# ARM2toARM3_FPA.net
KiCad netlist of a schematic drawn in Altium Designer
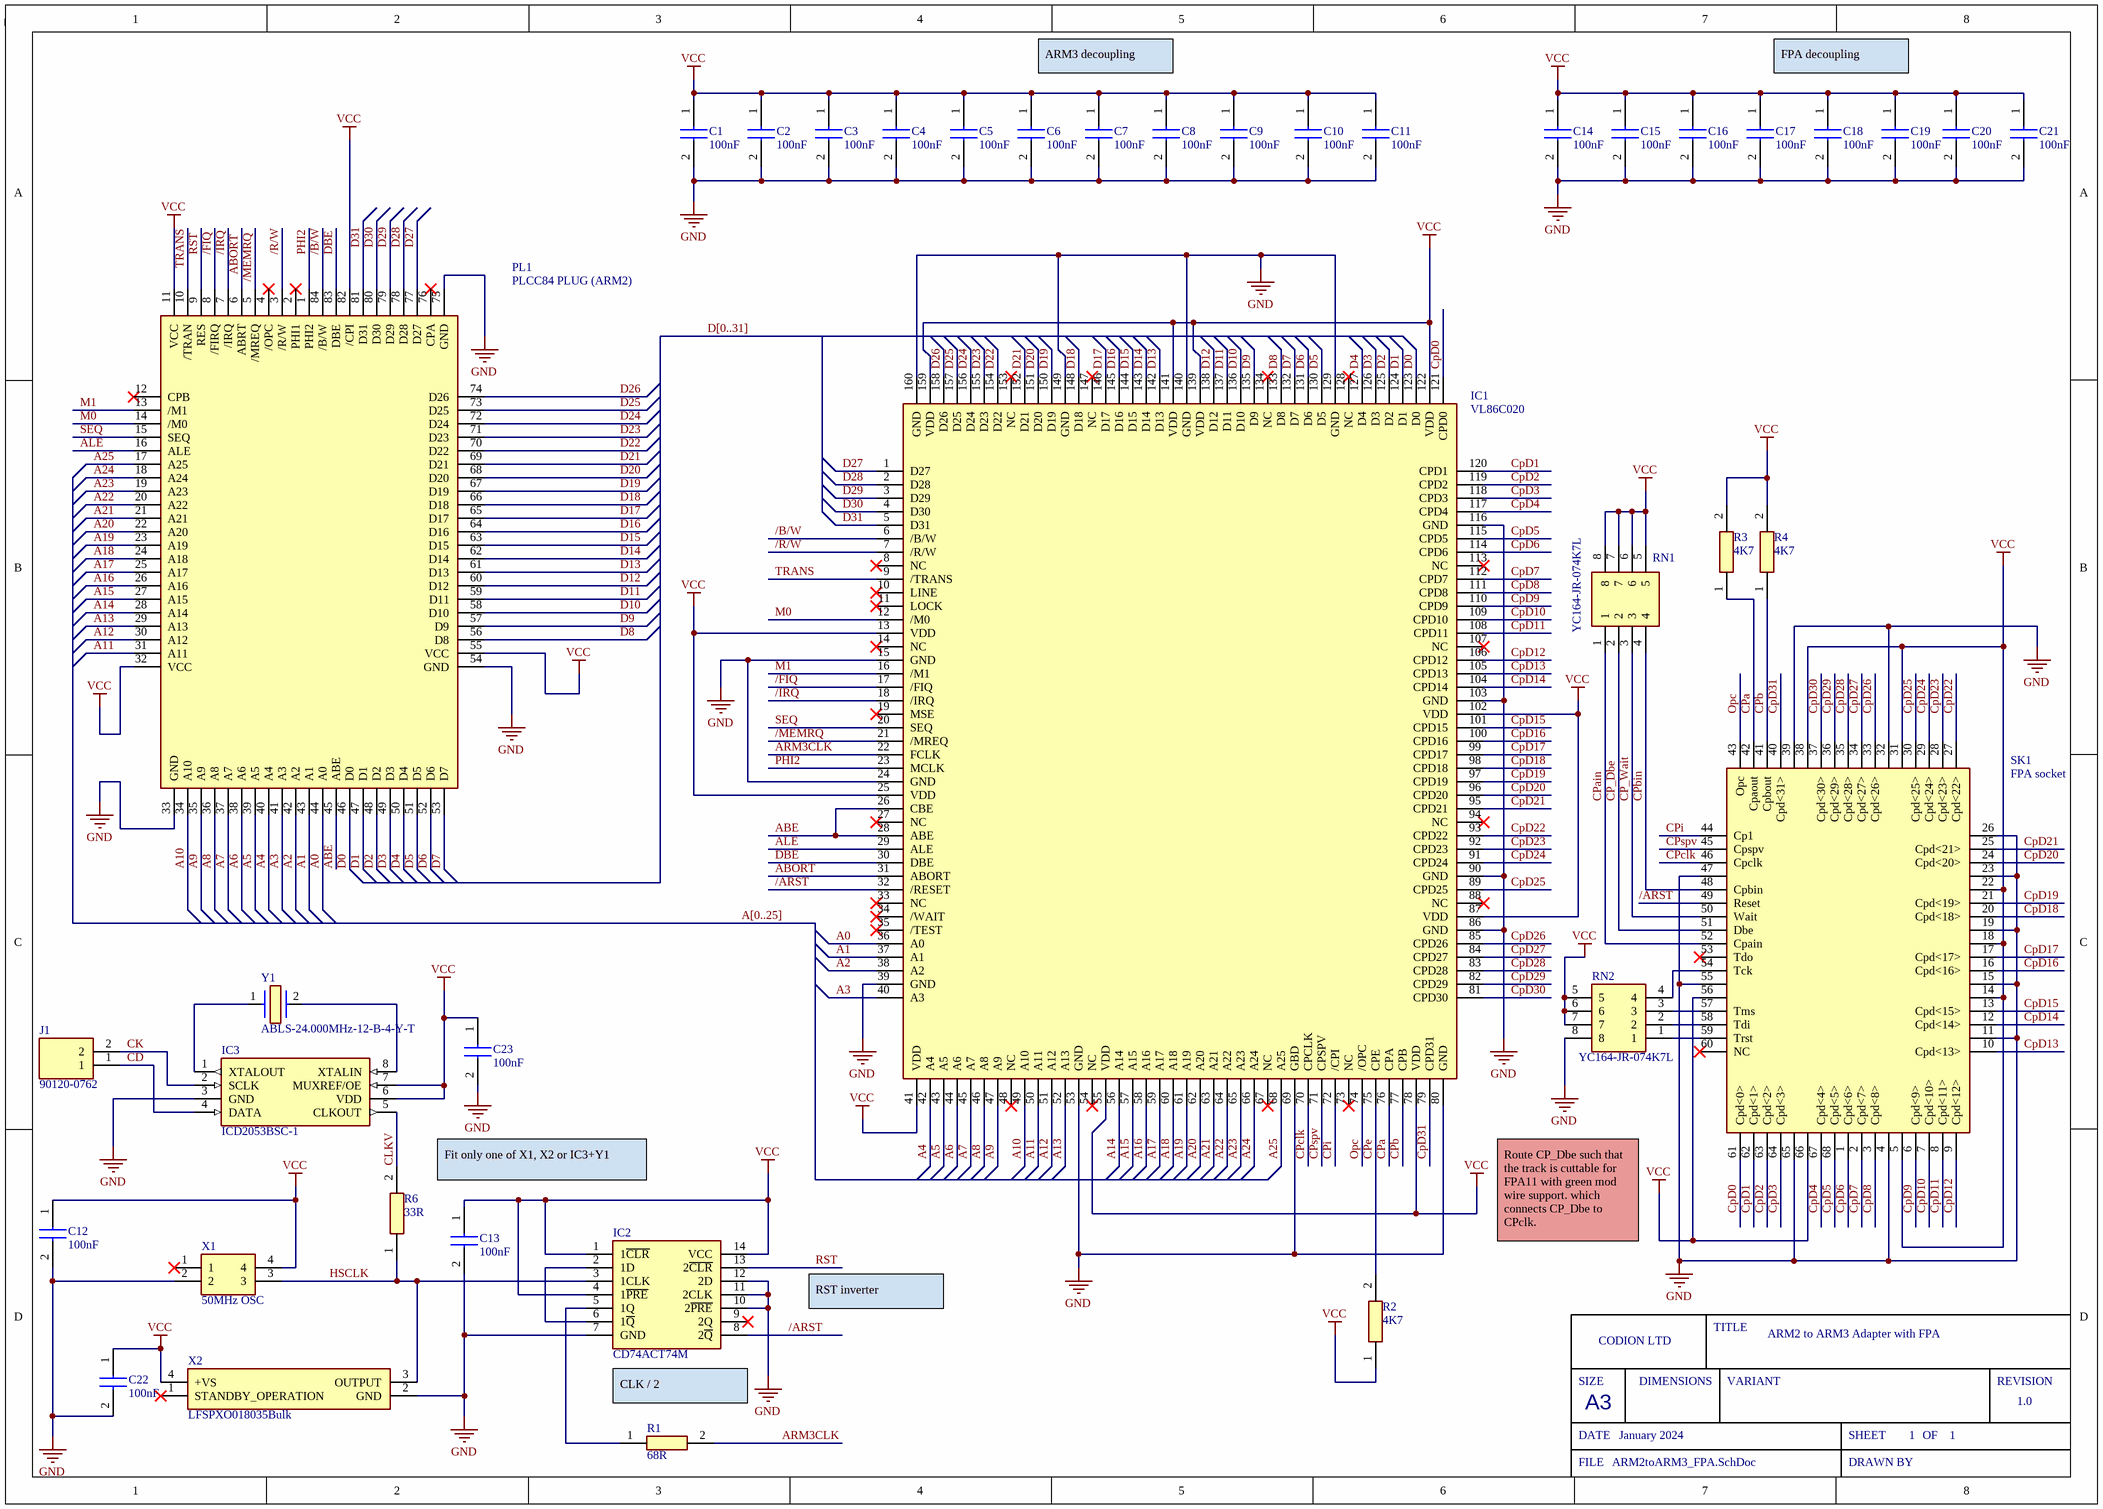
[diagram p0: ARM2toARM3_FPA.SchDoc]

(export (version "E")
  (design (tool "Eeschema 10.0.6"))
  (components
    (comp (ref "C1")
      (value "100nF")
      (footprint "SamacSys:CAPC2012X145N")
      (description "Capacitor")
      (fields
        (field (name "MANUFACTURER_PART_NUMBER") "C2012X7R1H104K125AM")
        (field (name "MOUSER PART NUMBER") "810-C2012X7R1H104KT5")
      )
      (libsource (lib "*") (part "C2012X7R1H104K125AM"))
    )
    (comp (ref "C2")
      (value "100nF")
      (footprint "SamacSys:CAPC2012X145N")
      (description "Capacitor")
      (fields
        (field (name "MANUFACTURER_PART_NUMBER") "C2012X7R1H104K125AM")
        (field (name "MOUSER PART NUMBER") "810-C2012X7R1H104KT5")
      )
      (libsource (lib "*") (part "C2012X7R1H104K125AM"))
    )
    (comp (ref "C3")
      (value "100nF")
      (footprint "SamacSys:CAPC2012X145N")
      (description "Capacitor")
      (fields
        (field (name "MANUFACTURER_PART_NUMBER") "C2012X7R1H104K125AM")
        (field (name "MOUSER PART NUMBER") "810-C2012X7R1H104KT5")
      )
      (libsource (lib "*") (part "C2012X7R1H104K125AM"))
    )
    (comp (ref "C4")
      (value "100nF")
      (footprint "SamacSys:CAPC2012X145N")
      (description "Capacitor")
      (fields
        (field (name "MANUFACTURER_PART_NUMBER") "C2012X7R1H104K125AM")
        (field (name "MOUSER PART NUMBER") "810-C2012X7R1H104KT5")
      )
      (libsource (lib "*") (part "C2012X7R1H104K125AM"))
    )
    (comp (ref "C5")
      (value "100nF")
      (footprint "SamacSys:CAPC2012X145N")
      (description "Capacitor")
      (fields
        (field (name "MANUFACTURER_PART_NUMBER") "C2012X7R1H104K125AM")
        (field (name "MOUSER PART NUMBER") "810-C2012X7R1H104KT5")
      )
      (libsource (lib "*") (part "C2012X7R1H104K125AM"))
    )
    (comp (ref "C6")
      (value "100nF")
      (footprint "SamacSys:CAPC2012X145N")
      (description "Capacitor")
      (fields
        (field (name "MANUFACTURER_PART_NUMBER") "C2012X7R1H104K125AM")
        (field (name "MOUSER PART NUMBER") "810-C2012X7R1H104KT5")
      )
      (libsource (lib "*") (part "C2012X7R1H104K125AM"))
    )
    (comp (ref "C7")
      (value "100nF")
      (footprint "SamacSys:CAPC2012X145N")
      (description "Capacitor")
      (fields
        (field (name "MANUFACTURER_PART_NUMBER") "C2012X7R1H104K125AM")
        (field (name "MOUSER PART NUMBER") "810-C2012X7R1H104KT5")
      )
      (libsource (lib "*") (part "C2012X7R1H104K125AM"))
    )
    (comp (ref "C8")
      (value "100nF")
      (footprint "SamacSys:CAPC2012X145N")
      (description "Capacitor")
      (fields
        (field (name "MANUFACTURER_PART_NUMBER") "C2012X7R1H104K125AM")
        (field (name "MOUSER PART NUMBER") "810-C2012X7R1H104KT5")
      )
      (libsource (lib "*") (part "C2012X7R1H104K125AM"))
    )
    (comp (ref "C9")
      (value "100nF")
      (footprint "SamacSys:CAPC2012X145N")
      (description "Capacitor")
      (fields
        (field (name "MANUFACTURER_PART_NUMBER") "C2012X7R1H104K125AM")
        (field (name "MOUSER PART NUMBER") "810-C2012X7R1H104KT5")
      )
      (libsource (lib "*") (part "C2012X7R1H104K125AM"))
    )
    (comp (ref "C10")
      (value "100nF")
      (footprint "SamacSys:CAPC2012X145N")
      (description "Capacitor")
      (fields
        (field (name "MANUFACTURER_PART_NUMBER") "C2012X7R1H104K125AM")
        (field (name "MOUSER PART NUMBER") "810-C2012X7R1H104KT5")
      )
      (libsource (lib "*") (part "C2012X7R1H104K125AM"))
    )
    (comp (ref "C11")
      (value "100nF")
      (footprint "SamacSys:CAPC2012X145N")
      (description "Capacitor")
      (fields
        (field (name "MANUFACTURER_PART_NUMBER") "C2012X7R1H104K125AM")
        (field (name "MOUSER PART NUMBER") "810-C2012X7R1H104KT5")
      )
      (libsource (lib "*") (part "C2012X7R1H104K125AM"))
    )
    (comp (ref "C12")
      (value "100nF")
      (footprint "SamacSys:CAPC2012X145N")
      (description "Capacitor")
      (fields
        (field (name "MANUFACTURER_PART_NUMBER") "C2012X7R1H104K125AM")
        (field (name "MOUSER PART NUMBER") "810-C2012X7R1H104KT5")
      )
      (libsource (lib "*") (part "C2012X7R1H104K125AM"))
    )
    (comp (ref "C13")
      (value "100nF")
      (footprint "SamacSys:CAPC2012X145N")
      (description "Capacitor")
      (fields
        (field (name "MANUFACTURER_PART_NUMBER") "C2012X7R1H104K125AM")
        (field (name "MOUSER PART NUMBER") "810-C2012X7R1H104KT5")
      )
      (libsource (lib "*") (part "C2012X7R1H104K125AM"))
    )
    (comp (ref "C14")
      (value "100nF")
      (footprint "SamacSys:CAPC2012X145N")
      (description "Capacitor")
      (fields
        (field (name "MANUFACTURER_PART_NUMBER") "C2012X7R1H104K125AM")
        (field (name "MOUSER PART NUMBER") "810-C2012X7R1H104KT5")
      )
      (libsource (lib "*") (part "C2012X7R1H104K125AM"))
    )
    (comp (ref "C15")
      (value "100nF")
      (footprint "SamacSys:CAPC2012X145N")
      (description "Capacitor")
      (fields
        (field (name "MANUFACTURER_PART_NUMBER") "C2012X7R1H104K125AM")
        (field (name "MOUSER PART NUMBER") "810-C2012X7R1H104KT5")
      )
      (libsource (lib "*") (part "C2012X7R1H104K125AM"))
    )
    (comp (ref "C16")
      (value "100nF")
      (footprint "SamacSys:CAPC2012X145N")
      (description "Capacitor")
      (fields
        (field (name "MANUFACTURER_PART_NUMBER") "C2012X7R1H104K125AM")
        (field (name "MOUSER PART NUMBER") "810-C2012X7R1H104KT5")
      )
      (libsource (lib "*") (part "C2012X7R1H104K125AM"))
    )
    (comp (ref "C17")
      (value "100nF")
      (footprint "SamacSys:CAPC2012X145N")
      (description "Capacitor")
      (fields
        (field (name "MANUFACTURER_PART_NUMBER") "C2012X7R1H104K125AM")
        (field (name "MOUSER PART NUMBER") "810-C2012X7R1H104KT5")
      )
      (libsource (lib "*") (part "C2012X7R1H104K125AM"))
    )
    (comp (ref "C18")
      (value "100nF")
      (footprint "SamacSys:CAPC2012X145N")
      (description "Capacitor")
      (fields
        (field (name "MANUFACTURER_PART_NUMBER") "C2012X7R1H104K125AM")
        (field (name "MOUSER PART NUMBER") "810-C2012X7R1H104KT5")
      )
      (libsource (lib "*") (part "C2012X7R1H104K125AM"))
    )
    (comp (ref "C19")
      (value "100nF")
      (footprint "SamacSys:CAPC2012X145N")
      (description "Capacitor")
      (fields
        (field (name "MANUFACTURER_PART_NUMBER") "C2012X7R1H104K125AM")
        (field (name "MOUSER PART NUMBER") "810-C2012X7R1H104KT5")
      )
      (libsource (lib "*") (part "C2012X7R1H104K125AM"))
    )
    (comp (ref "C20")
      (value "100nF")
      (footprint "SamacSys:CAPC2012X145N")
      (description "Capacitor")
      (fields
        (field (name "MANUFACTURER_PART_NUMBER") "C2012X7R1H104K125AM")
        (field (name "MOUSER PART NUMBER") "810-C2012X7R1H104KT5")
      )
      (libsource (lib "*") (part "C2012X7R1H104K125AM"))
    )
    (comp (ref "C21")
      (value "100nF")
      (footprint "SamacSys:CAPC2012X145N")
      (description "Capacitor")
      (fields
        (field (name "MANUFACTURER_PART_NUMBER") "C2012X7R1H104K125AM")
        (field (name "MOUSER PART NUMBER") "810-C2012X7R1H104KT5")
      )
      (libsource (lib "*") (part "C2012X7R1H104K125AM"))
    )
    (comp (ref "C22")
      (value "100nF")
      (footprint "SamacSys:CAPC2012X145N")
      (description "Capacitor")
      (fields
        (field (name "MANUFACTURER_PART_NUMBER") "C2012X7R1H104K125AM")
        (field (name "MOUSER PART NUMBER") "810-C2012X7R1H104KT5")
      )
      (libsource (lib "*") (part "C2012X7R1H104K125AM"))
    )
    (comp (ref "C23")
      (value "100nF")
      (footprint "SamacSys:CAPC2012X145N")
      (description "Capacitor")
      (fields
        (field (name "MANUFACTURER_PART_NUMBER") "C2012X7R1H104K125AM")
        (field (name "MOUSER PART NUMBER") "810-C2012X7R1H104KT5")
      )
      (libsource (lib "*") (part "C2012X7R1H104K125AM"))
    )
    (comp (ref "IC1")
      (value "VL86C020")
      (footprint "SamacSys:QFP65P3120X3120X407-160N")
      (description "ARM3")
      (fields (field (name "MANUFACTURER_PART_NUMBER") "VL86C)20"))
      (libsource (lib "*") (part "SAA7146AH_V4,557"))
    )
    (comp (ref "IC2")
      (value "CD74ACT74M")
      (footprint "SamacSys:SOIC127P600X175-14N")
      (description "Integrated Circuit")
      (fields (field (name "MOUSER PART NUMBER") "595-CD74ACT74M"))
      (libsource (lib "*") (part "CD74ACT74M"))
    )
    (comp (ref "IC3")
      (value "ICD2053BSC-1")
      (footprint "SamacSys:SOIC127P602X173-8N")
      (description "Integrated Circuit")
      (libsource (lib "*") (part "ICD2053BSC-1"))
    )
    (comp (ref "J1")
      (value "90120-0762")
      (footprint "SamacSys:HDRV2W35P0X254_1X2_508X249X560P")
      (description "Connector")
      (fields (field (name "MOUSER PART NUMBER") "538-90120-0762"))
      (libsource (lib "SamacSys") (part "90120-0762"))
    )
    (comp (ref "PL1")
      (value "PLCC84 PLUG (ARM2)")
      (footprint "PLCC84_PLUG")
      (description "PLCC84 Plug")
      (fields (field (name "MANUFACTURER_PART_NUMBER") "W9328"))
      (libsource (lib "ARM2toARM3Adapter") (part "PLCC84_PLUG_ARM2"))
    )
    (comp (ref "R1")
      (value "68R")
      (footprint "SamacSys:RESC2012X50N")
      (description "68R Resistor")
      (fields
        (field (name "MANUFACTURER_PART_NUMBER") "CRCW080568R0FKEA")
        (field (name "MOUSER PART NUMBER") "71-CRCW080568R0FKEA")
      )
      (libsource (lib "*") (part "CRCW080568R0FKEA"))
    )
    (comp (ref "R2")
      (value "4K7")
      (footprint "SamacSys:RESC1005X40N")
      (description "Resistor")
      (fields
        (field (name "MANUFACTURER_PART_NUMBER") "CRCW04024K70FKEDHP")
        (field (name "MOUSER PART NUMBER") "71-CRCW04024K70FKEDH")
      )
      (libsource (lib "*") (part "CRCW04024K70FKEDHP"))
    )
    (comp (ref "R3")
      (value "4K7")
      (footprint "SamacSys:RESC1005X40N")
      (description "Resistor")
      (fields
        (field (name "MANUFACTURER_PART_NUMBER") "CRCW04024K70FKEDHP")
        (field (name "MOUSER PART NUMBER") "71-CRCW04024K70FKEDH")
      )
      (libsource (lib "*") (part "CRCW04024K70FKEDHP"))
    )
    (comp (ref "R4")
      (value "4K7")
      (footprint "SamacSys:RESC1005X40N")
      (description "Resistor")
      (fields
        (field (name "MANUFACTURER_PART_NUMBER") "CRCW04024K70FKEDHP")
        (field (name "MOUSER PART NUMBER") "71-CRCW04024K70FKEDH")
      )
      (libsource (lib "*") (part "CRCW04024K70FKEDHP"))
    )
    (comp (ref "R6")
      (value "33R")
      (footprint "SamacSys:RESC1005X40N")
      (description "Resistor")
      (fields
        (field (name "MANUFACTURER_PART_NUMBER") "CRCW040233R0FKED")
        (field (name "MOUSER PART NUMBER") "71-CRCW0402-33-E3")
      )
      (libsource (lib "SamacSys") (part "CRCW040233R0FKED"))
    )
    (comp (ref "RN1")
      (value "YC164-JR-074K7L")
      (footprint "SamacSys:YC164JR07220RL")
      (description "Resistor Network")
      (fields (field (name "MOUSER PART NUMBER") "603-YC164-JR-074K7L"))
      (libsource (lib "*") (part "YC164-JR-074K7L"))
    )
    (comp (ref "RN2")
      (value "YC164-JR-074K7L")
      (footprint "SamacSys:YC164JR07220RL")
      (description "Resistor Network")
      (fields (field (name "MOUSER PART NUMBER") "603-YC164-JR-074K7L"))
      (libsource (lib "") (part "YC164-JR-074K7L_1"))
    )
    (comp (ref "SK1")
      (value "FPA socket")
      (footprint "Acorn:MEMC_Socket")
      (fields
        (field (name "MANUFACTURER_PART_NUMBER") "8468-21B1-RK-TR")
        (field (name "MOUSER PART NUMBER") "517-8468-21B1-RK-TR")
      )
      (libsource (lib "Acorn") (part "FPA_SKT"))
    )
    (comp (ref "X1")
      (value "50MHz OSC")
      (footprint "SamacSys:DIPS762W56P1524L1778H241Q4N")
      (fields
        (field (name "MANUFACTURER_PART_NUMBER") "1107741")
        (field (name "MOUSER PART NUMBER") "535-1107741")
      )
      (libsource (lib "*") (part "1107741"))
    )
    (comp (ref "X2")
      (value "LFSPXO018035Bulk")
      (footprint "SamacSys:LFSPXO018035Bulk")
      (description "Crystal or Oscillator")
      (fields (field (name "MOUSER PART NUMBER") "449-LFSPXO018035BULK"))
      (libsource (lib "*") (part "LFSPXO018035Bulk"))
    )
    (comp (ref "Y1")
      (value "ABLS-24.000MHz-12-B-4-Y-T")
      (footprint "SamacSys:ABLS")
      (description "Crystal or Oscillator")
      (libsource (lib "*") (part "ABLS-24.000MHz-12-B-4-Y-T"))
    )
  )
  (nets
    (net (code "1") (name "/A0") (class "Default")
      (node (ref "IC1") (pin "36") (pinfunction "A0_36") (pintype "passive"))
      (node (ref "PL1") (pin "44") (pinfunction "A0_44") (pintype "passive"))
    )
    (net (code "2") (name "/A1") (class "Default")
      (node (ref "IC1") (pin "37") (pinfunction "A1_37") (pintype "passive"))
      (node (ref "PL1") (pin "43") (pinfunction "A1_43") (pintype "passive"))
    )
    (net (code "3") (name "/A2") (class "Default")
      (node (ref "IC1") (pin "38") (pinfunction "A2_38") (pintype "passive"))
      (node (ref "PL1") (pin "42") (pinfunction "A2_42") (pintype "passive"))
    )
    (net (code "4") (name "/A3") (class "Default")
      (node (ref "IC1") (pin "40") (pinfunction "A3_40") (pintype "passive"))
      (node (ref "PL1") (pin "41") (pinfunction "A3_41") (pintype "passive"))
    )
    (net (code "5") (name "/A4") (class "Default")
      (node (ref "IC1") (pin "42") (pinfunction "A4_42") (pintype "passive"))
      (node (ref "PL1") (pin "40") (pinfunction "A4_40") (pintype "passive"))
    )
    (net (code "6") (name "/A5") (class "Default")
      (node (ref "IC1") (pin "43") (pinfunction "A5_43") (pintype "passive"))
      (node (ref "PL1") (pin "39") (pinfunction "A5_39") (pintype "passive"))
    )
    (net (code "7") (name "/A6") (class "Default")
      (node (ref "IC1") (pin "44") (pinfunction "A6_44") (pintype "passive"))
      (node (ref "PL1") (pin "38") (pinfunction "A6_38") (pintype "passive"))
    )
    (net (code "8") (name "/A7") (class "Default")
      (node (ref "IC1") (pin "45") (pinfunction "A7_45") (pintype "passive"))
      (node (ref "PL1") (pin "37") (pinfunction "A7_37") (pintype "passive"))
    )
    (net (code "9") (name "/A8") (class "Default")
      (node (ref "IC1") (pin "46") (pinfunction "A8_46") (pintype "passive"))
      (node (ref "PL1") (pin "36") (pinfunction "A8_36") (pintype "passive"))
    )
    (net (code "10") (name "/A9") (class "Default")
      (node (ref "IC1") (pin "47") (pinfunction "A9_47") (pintype "passive"))
      (node (ref "PL1") (pin "35") (pinfunction "A9_35") (pintype "passive"))
    )
    (net (code "11") (name "/A10") (class "Default")
      (node (ref "IC1") (pin "49") (pinfunction "A10_49") (pintype "passive"))
      (node (ref "PL1") (pin "34") (pinfunction "A10_34") (pintype "passive"))
    )
    (net (code "12") (name "/A11") (class "Default")
      (node (ref "IC1") (pin "50") (pinfunction "A11_50") (pintype "passive"))
      (node (ref "PL1") (pin "31") (pinfunction "A11_31") (pintype "passive"))
    )
    (net (code "13") (name "/A12") (class "Default")
      (node (ref "IC1") (pin "51") (pinfunction "A12_51") (pintype "passive"))
      (node (ref "PL1") (pin "30") (pinfunction "A12_30") (pintype "passive"))
    )
    (net (code "14") (name "/A13") (class "Default")
      (node (ref "IC1") (pin "52") (pinfunction "A13_52") (pintype "passive"))
      (node (ref "PL1") (pin "29") (pinfunction "A13_29") (pintype "passive"))
    )
    (net (code "15") (name "/A14") (class "Default")
      (node (ref "IC1") (pin "56") (pinfunction "A14_56") (pintype "passive"))
      (node (ref "PL1") (pin "28") (pinfunction "A14_28") (pintype "passive"))
    )
    (net (code "16") (name "/A15") (class "Default")
      (node (ref "IC1") (pin "57") (pinfunction "A15_57") (pintype "passive"))
      (node (ref "PL1") (pin "27") (pinfunction "A15_27") (pintype "passive"))
    )
    (net (code "17") (name "/A16") (class "Default")
      (node (ref "IC1") (pin "58") (pinfunction "A16_58") (pintype "passive"))
      (node (ref "PL1") (pin "26") (pinfunction "A16_26") (pintype "passive"))
    )
    (net (code "18") (name "/A17") (class "Default")
      (node (ref "IC1") (pin "59") (pinfunction "A17_59") (pintype "passive"))
      (node (ref "PL1") (pin "25") (pinfunction "A17_25") (pintype "passive"))
    )
    (net (code "19") (name "/A18") (class "Default")
      (node (ref "IC1") (pin "60") (pinfunction "A18_60") (pintype "passive"))
      (node (ref "PL1") (pin "24") (pinfunction "A18_24") (pintype "passive"))
    )
    (net (code "20") (name "/A19") (class "Default")
      (node (ref "IC1") (pin "61") (pinfunction "A19_61") (pintype "passive"))
      (node (ref "PL1") (pin "23") (pinfunction "A19_23") (pintype "passive"))
    )
    (net (code "21") (name "/A20") (class "Default")
      (node (ref "IC1") (pin "62") (pinfunction "A20_62") (pintype "passive"))
      (node (ref "PL1") (pin "22") (pinfunction "A20_22") (pintype "passive"))
    )
    (net (code "22") (name "/A21") (class "Default")
      (node (ref "IC1") (pin "63") (pinfunction "A21_63") (pintype "passive"))
      (node (ref "PL1") (pin "21") (pinfunction "A21_21") (pintype "passive"))
    )
    (net (code "23") (name "/A22") (class "Default")
      (node (ref "IC1") (pin "64") (pinfunction "A22_64") (pintype "passive"))
      (node (ref "PL1") (pin "20") (pinfunction "A22_20") (pintype "passive"))
    )
    (net (code "24") (name "/A23") (class "Default")
      (node (ref "IC1") (pin "65") (pinfunction "A23_65") (pintype "passive"))
      (node (ref "PL1") (pin "19") (pinfunction "A23_19") (pintype "passive"))
    )
    (net (code "25") (name "/A24") (class "Default")
      (node (ref "IC1") (pin "66") (pinfunction "A24_66") (pintype "passive"))
      (node (ref "PL1") (pin "18") (pinfunction "A24_18") (pintype "passive"))
    )
    (net (code "26") (name "/A25") (class "Default")
      (node (ref "IC1") (pin "68") (pinfunction "A25_68") (pintype "passive"))
      (node (ref "PL1") (pin "17") (pinfunction "A25_17") (pintype "passive"))
    )
    (net (code "27") (name "/ABE") (class "Default")
      (node (ref "IC1") (pin "26") (pinfunction "CBE_26") (pintype "passive"))
      (node (ref "IC1") (pin "28") (pinfunction "ABE_28") (pintype "passive"))
      (node (ref "PL1") (pin "45") (pinfunction "ABE_45") (pintype "passive"))
    )
    (net (code "28") (name "/ABORT") (class "Default")
      (node (ref "IC1") (pin "31") (pinfunction "ABORT_31") (pintype "passive"))
      (node (ref "PL1") (pin "6") (pinfunction "ABRT_6") (pintype "passive"))
    )
    (net (code "29") (name "/ALE") (class "Default")
      (node (ref "IC1") (pin "29") (pinfunction "ALE_29") (pintype "passive"))
      (node (ref "PL1") (pin "16") (pinfunction "ALE_16") (pintype "passive"))
    )
    (net (code "30") (name "/ARM3CLK") (class "Default")
      (node (ref "IC1") (pin "22") (pinfunction "FCLK_22") (pintype "passive"))
      (node (ref "R1") (pin "2") (pinfunction "2_2") (pintype "passive"))
    )
    (net (code "32") (name "/CD") (class "Default")
      (node (ref "IC3") (pin "4") (pinfunction "DATA_4") (pintype "input"))
      (node (ref "J1") (pin "1") (pinfunction "1_1") (pintype "passive"))
    )
    (net (code "33") (name "/CK") (class "Default")
      (node (ref "IC3") (pin "2") (pinfunction "SCLK_2") (pintype "input"))
      (node (ref "J1") (pin "2") (pinfunction "2_2") (pintype "passive"))
    )
    (net (code "34") (name "/CLKV") (class "Default")
      (node (ref "IC3") (pin "5") (pinfunction "CLKOUT_5") (pintype "output"))
      (node (ref "R6") (pin "2") (pinfunction "2_2") (pintype "passive"))
    )
    (net (code "35") (name "/CP_Dbe") (class "Default")
      (node (ref "RN1") (pin "2") (pinfunction "2_2") (pintype "passive"))
      (node (ref "SK1") (pin "51") (pinfunction "Dbe_51") (pintype "passive"))
    )
    (net (code "36") (name "/CP_Wait") (class "Default")
      (node (ref "RN1") (pin "3") (pinfunction "3_3") (pintype "passive"))
      (node (ref "SK1") (pin "50") (pinfunction "Wait_50") (pintype "passive"))
    )
    (net (code "37") (name "/CPa") (class "Default")
      (node (ref "IC1") (pin "76") (pinfunction "CPA_76") (pintype "passive"))
      (node (ref "R3") (pin "1") (pinfunction "1_1") (pintype "passive"))
      (node (ref "SK1") (pin "42") (pinfunction "Cpaout_42") (pintype "passive"))
    )
    (net (code "38") (name "/CPain") (class "Default")
      (node (ref "RN1") (pin "1") (pinfunction "1_1") (pintype "passive"))
      (node (ref "SK1") (pin "52") (pinfunction "Cpain_52") (pintype "passive"))
    )
    (net (code "39") (name "/CPb") (class "Default")
      (node (ref "IC1") (pin "77") (pinfunction "CPB_77") (pintype "passive"))
      (node (ref "R4") (pin "1") (pinfunction "1_1") (pintype "passive"))
      (node (ref "SK1") (pin "41") (pinfunction "Cpbout_41") (pintype "passive"))
    )
    (net (code "40") (name "/CPbin") (class "Default")
      (node (ref "RN1") (pin "4") (pinfunction "4_4") (pintype "passive"))
      (node (ref "SK1") (pin "48") (pinfunction "Cpbin_48") (pintype "passive"))
    )
    (net (code "41") (name "/CPclk") (class "Default")
      (node (ref "IC1") (pin "70") (pinfunction "CPCLK_70") (pintype "passive"))
      (node (ref "SK1") (pin "46") (pinfunction "Cpclk_46") (pintype "passive"))
    )
    (net (code "42") (name "/CPe") (class "Default")
      (node (ref "IC1") (pin "75") (pinfunction "CPE_75") (pintype "passive"))
      (node (ref "R2") (pin "2") (pinfunction "2_2") (pintype "passive"))
    )
    (net (code "43") (name "/CPi") (class "Default")
      (node (ref "IC1") (pin "72") (pinfunction "/CPI_72") (pintype "passive"))
      (node (ref "SK1") (pin "44") (pinfunction "Cp1_44") (pintype "passive"))
    )
    (net (code "44") (name "/CPspv") (class "Default")
      (node (ref "IC1") (pin "71") (pinfunction "CPSPV_71") (pintype "passive"))
      (node (ref "SK1") (pin "45") (pinfunction "Cpspv_45") (pintype "passive"))
    )
    (net (code "45") (name "/CpD0") (class "Default")
      (node (ref "IC1") (pin "121") (pinfunction "CPD0_121") (pintype "passive"))
      (node (ref "SK1") (pin "61") (pinfunction "Cpd<0>_61") (pintype "passive"))
    )
    (net (code "46") (name "/CpD1") (class "Default")
      (node (ref "IC1") (pin "120") (pinfunction "CPD1_120") (pintype "passive"))
      (node (ref "SK1") (pin "62") (pinfunction "Cpd<1>_62") (pintype "passive"))
    )
    (net (code "47") (name "/CpD2") (class "Default")
      (node (ref "IC1") (pin "119") (pinfunction "CPD2_119") (pintype "passive"))
      (node (ref "SK1") (pin "63") (pinfunction "Cpd<2>_63") (pintype "passive"))
    )
    (net (code "48") (name "/CpD3") (class "Default")
      (node (ref "IC1") (pin "118") (pinfunction "CPD3_118") (pintype "passive"))
      (node (ref "SK1") (pin "64") (pinfunction "Cpd<3>_64") (pintype "passive"))
    )
    (net (code "49") (name "/CpD4") (class "Default")
      (node (ref "IC1") (pin "117") (pinfunction "CPD4_117") (pintype "passive"))
      (node (ref "SK1") (pin "67") (pinfunction "Cpd<4>_67") (pintype "passive"))
    )
    (net (code "50") (name "/CpD5") (class "Default")
      (node (ref "IC1") (pin "115") (pinfunction "CPD5_115") (pintype "passive"))
      (node (ref "SK1") (pin "68") (pinfunction "Cpd<5>_68") (pintype "passive"))
    )
    (net (code "51") (name "/CpD6") (class "Default")
      (node (ref "IC1") (pin "114") (pinfunction "CPD6_114") (pintype "passive"))
      (node (ref "SK1") (pin "1") (pinfunction "Cpd<6>_1") (pintype "passive"))
    )
    (net (code "52") (name "/CpD7") (class "Default")
      (node (ref "IC1") (pin "112") (pinfunction "CPD7_112") (pintype "passive"))
      (node (ref "SK1") (pin "2") (pinfunction "Cpd<7>_2") (pintype "passive"))
    )
    (net (code "53") (name "/CpD8") (class "Default")
      (node (ref "IC1") (pin "111") (pinfunction "CPD8_111") (pintype "passive"))
      (node (ref "SK1") (pin "3") (pinfunction "Cpd<8>_3") (pintype "passive"))
    )
    (net (code "54") (name "/CpD9") (class "Default")
      (node (ref "IC1") (pin "110") (pinfunction "CPD9_110") (pintype "passive"))
      (node (ref "SK1") (pin "6") (pinfunction "Cpd<9>_6") (pintype "passive"))
    )
    (net (code "55") (name "/CpD10") (class "Default")
      (node (ref "IC1") (pin "109") (pinfunction "CPD10_109") (pintype "passive"))
      (node (ref "SK1") (pin "7") (pinfunction "Cpd<10>_7") (pintype "passive"))
    )
    (net (code "56") (name "/CpD11") (class "Default")
      (node (ref "IC1") (pin "108") (pinfunction "CPD11_108") (pintype "passive"))
      (node (ref "SK1") (pin "8") (pinfunction "Cpd<11>_8") (pintype "passive"))
    )
    (net (code "57") (name "/CpD12") (class "Default")
      (node (ref "IC1") (pin "106") (pinfunction "CPD12_106") (pintype "passive"))
      (node (ref "SK1") (pin "9") (pinfunction "Cpd<12>_9") (pintype "passive"))
    )
    (net (code "58") (name "/CpD13") (class "Default")
      (node (ref "IC1") (pin "105") (pinfunction "CPD13_105") (pintype "passive"))
      (node (ref "SK1") (pin "10") (pinfunction "Cpd<13>_10") (pintype "passive"))
    )
    (net (code "59") (name "/CpD14") (class "Default")
      (node (ref "IC1") (pin "104") (pinfunction "CPD14_104") (pintype "passive"))
      (node (ref "SK1") (pin "12") (pinfunction "Cpd<14>_12") (pintype "passive"))
    )
    (net (code "60") (name "/CpD15") (class "Default")
      (node (ref "IC1") (pin "101") (pinfunction "CPD15_101") (pintype "passive"))
      (node (ref "SK1") (pin "13") (pinfunction "Cpd<15>_13") (pintype "passive"))
    )
    (net (code "61") (name "/CpD16") (class "Default")
      (node (ref "IC1") (pin "100") (pinfunction "CPD16_100") (pintype "passive"))
      (node (ref "SK1") (pin "16") (pinfunction "Cpd<16>_16") (pintype "passive"))
    )
    (net (code "62") (name "/CpD17") (class "Default")
      (node (ref "IC1") (pin "99") (pinfunction "CPD17_99") (pintype "passive"))
      (node (ref "SK1") (pin "17") (pinfunction "Cpd<17>_17") (pintype "passive"))
    )
    (net (code "63") (name "/CpD18") (class "Default")
      (node (ref "IC1") (pin "98") (pinfunction "CPD18_98") (pintype "passive"))
      (node (ref "SK1") (pin "20") (pinfunction "Cpd<18>_20") (pintype "passive"))
    )
    (net (code "64") (name "/CpD19") (class "Default")
      (node (ref "IC1") (pin "97") (pinfunction "CPD19_97") (pintype "passive"))
      (node (ref "SK1") (pin "21") (pinfunction "Cpd<19>_21") (pintype "passive"))
    )
    (net (code "65") (name "/CpD20") (class "Default")
      (node (ref "IC1") (pin "96") (pinfunction "CPD20_96") (pintype "passive"))
      (node (ref "SK1") (pin "24") (pinfunction "Cpd<20>_24") (pintype "passive"))
    )
    (net (code "66") (name "/CpD21") (class "Default")
      (node (ref "IC1") (pin "95") (pinfunction "CPD21_95") (pintype "passive"))
      (node (ref "SK1") (pin "25") (pinfunction "Cpd<21>_25") (pintype "passive"))
    )
    (net (code "67") (name "/CpD22") (class "Default")
      (node (ref "IC1") (pin "93") (pinfunction "CPD22_93") (pintype "passive"))
      (node (ref "SK1") (pin "27") (pinfunction "Cpd<22>_27") (pintype "passive"))
    )
    (net (code "68") (name "/CpD23") (class "Default")
      (node (ref "IC1") (pin "92") (pinfunction "CPD23_92") (pintype "passive"))
      (node (ref "SK1") (pin "28") (pinfunction "Cpd<23>_28") (pintype "passive"))
    )
    (net (code "69") (name "/CpD24") (class "Default")
      (node (ref "IC1") (pin "91") (pinfunction "CPD24_91") (pintype "passive"))
      (node (ref "SK1") (pin "29") (pinfunction "Cpd<24>_29") (pintype "passive"))
    )
    (net (code "70") (name "/CpD25") (class "Default")
      (node (ref "IC1") (pin "89") (pinfunction "CPD25_89") (pintype "passive"))
      (node (ref "SK1") (pin "30") (pinfunction "Cpd<25>_30") (pintype "passive"))
    )
    (net (code "71") (name "/CpD26") (class "Default")
      (node (ref "IC1") (pin "85") (pinfunction "CPD26_85") (pintype "passive"))
      (node (ref "SK1") (pin "33") (pinfunction "Cpd<26>_33") (pintype "passive"))
    )
    (net (code "72") (name "/CpD27") (class "Default")
      (node (ref "IC1") (pin "84") (pinfunction "CPD27_84") (pintype "passive"))
      (node (ref "SK1") (pin "34") (pinfunction "Cpd<27>_34") (pintype "passive"))
    )
    (net (code "73") (name "/CpD28") (class "Default")
      (node (ref "IC1") (pin "83") (pinfunction "CPD28_83") (pintype "passive"))
      (node (ref "SK1") (pin "35") (pinfunction "Cpd<28>_35") (pintype "passive"))
    )
    (net (code "74") (name "/CpD29") (class "Default")
      (node (ref "IC1") (pin "82") (pinfunction "CPD29_82") (pintype "passive"))
      (node (ref "SK1") (pin "36") (pinfunction "Cpd<29>_36") (pintype "passive"))
    )
    (net (code "75") (name "/CpD30") (class "Default")
      (node (ref "IC1") (pin "81") (pinfunction "CPD30_81") (pintype "passive"))
      (node (ref "SK1") (pin "37") (pinfunction "Cpd<30>_37") (pintype "passive"))
    )
    (net (code "76") (name "/CpD31") (class "Default")
      (node (ref "IC1") (pin "79") (pinfunction "CPD31_79") (pintype "passive"))
      (node (ref "SK1") (pin "40") (pinfunction "Cpd<31>_40") (pintype "passive"))
    )
    (net (code "77") (name "/D0") (class "Default")
      (node (ref "IC1") (pin "123") (pinfunction "D0_123") (pintype "passive"))
      (node (ref "PL1") (pin "46") (pinfunction "D0_46") (pintype "passive"))
    )
    (net (code "78") (name "/D1") (class "Default")
      (node (ref "IC1") (pin "124") (pinfunction "D1_124") (pintype "passive"))
      (node (ref "PL1") (pin "47") (pinfunction "D1_47") (pintype "passive"))
    )
    (net (code "79") (name "/D2") (class "Default")
      (node (ref "IC1") (pin "125") (pinfunction "D2_125") (pintype "passive"))
      (node (ref "PL1") (pin "48") (pinfunction "D2_48") (pintype "passive"))
    )
    (net (code "80") (name "/D3") (class "Default")
      (node (ref "IC1") (pin "126") (pinfunction "D3_126") (pintype "passive"))
      (node (ref "PL1") (pin "49") (pinfunction "D3_49") (pintype "passive"))
    )
    (net (code "81") (name "/D4") (class "Default")
      (node (ref "IC1") (pin "127") (pinfunction "D4_127") (pintype "passive"))
      (node (ref "PL1") (pin "50") (pinfunction "D4_50") (pintype "passive"))
    )
    (net (code "82") (name "/D5") (class "Default")
      (node (ref "IC1") (pin "130") (pinfunction "D5_130") (pintype "passive"))
      (node (ref "PL1") (pin "51") (pinfunction "D5_51") (pintype "passive"))
    )
    (net (code "83") (name "/D6") (class "Default")
      (node (ref "IC1") (pin "131") (pinfunction "D6_131") (pintype "passive"))
      (node (ref "PL1") (pin "52") (pinfunction "D6_52") (pintype "passive"))
    )
    (net (code "84") (name "/D7") (class "Default")
      (node (ref "IC1") (pin "132") (pinfunction "D7_132") (pintype "passive"))
      (node (ref "PL1") (pin "53") (pinfunction "D7_53") (pintype "passive"))
    )
    (net (code "85") (name "/D8") (class "Default")
      (node (ref "IC1") (pin "133") (pinfunction "D8_133") (pintype "passive"))
      (node (ref "PL1") (pin "56") (pinfunction "D8_56") (pintype "passive"))
    )
    (net (code "86") (name "/D9") (class "Default")
      (node (ref "IC1") (pin "135") (pinfunction "D9_135") (pintype "passive"))
      (node (ref "PL1") (pin "57") (pinfunction "D9_57") (pintype "passive"))
    )
    (net (code "87") (name "/D10") (class "Default")
      (node (ref "IC1") (pin "136") (pinfunction "D10_136") (pintype "passive"))
      (node (ref "PL1") (pin "58") (pinfunction "D10_58") (pintype "passive"))
    )
    (net (code "88") (name "/D11") (class "Default")
      (node (ref "IC1") (pin "137") (pinfunction "D11_137") (pintype "passive"))
      (node (ref "PL1") (pin "59") (pinfunction "D11_59") (pintype "passive"))
    )
    (net (code "89") (name "/D12") (class "Default")
      (node (ref "IC1") (pin "138") (pinfunction "D12_138") (pintype "passive"))
      (node (ref "PL1") (pin "60") (pinfunction "D12_60") (pintype "passive"))
    )
    (net (code "90") (name "/D13") (class "Default")
      (node (ref "IC1") (pin "142") (pinfunction "D13_142") (pintype "passive"))
      (node (ref "PL1") (pin "61") (pinfunction "D13_61") (pintype "passive"))
    )
    (net (code "91") (name "/D14") (class "Default")
      (node (ref "IC1") (pin "143") (pinfunction "D14_143") (pintype "passive"))
      (node (ref "PL1") (pin "62") (pinfunction "D14_62") (pintype "passive"))
    )
    (net (code "92") (name "/D15") (class "Default")
      (node (ref "IC1") (pin "144") (pinfunction "D15_144") (pintype "passive"))
      (node (ref "PL1") (pin "63") (pinfunction "D15_63") (pintype "passive"))
    )
    (net (code "93") (name "/D16") (class "Default")
      (node (ref "IC1") (pin "145") (pinfunction "D16_145") (pintype "passive"))
      (node (ref "PL1") (pin "64") (pinfunction "D16_64") (pintype "passive"))
    )
    (net (code "94") (name "/D17") (class "Default")
      (node (ref "IC1") (pin "146") (pinfunction "D17_146") (pintype "passive"))
      (node (ref "PL1") (pin "65") (pinfunction "D17_65") (pintype "passive"))
    )
    (net (code "95") (name "/D18") (class "Default")
      (node (ref "IC1") (pin "148") (pinfunction "D18_148") (pintype "passive"))
      (node (ref "PL1") (pin "66") (pinfunction "D18_66") (pintype "passive"))
    )
    (net (code "96") (name "/D19") (class "Default")
      (node (ref "IC1") (pin "150") (pinfunction "D19_150") (pintype "passive"))
      (node (ref "PL1") (pin "67") (pinfunction "D19_67") (pintype "passive"))
    )
    (net (code "97") (name "/D20") (class "Default")
      (node (ref "IC1") (pin "151") (pinfunction "D20_151") (pintype "passive"))
      (node (ref "PL1") (pin "68") (pinfunction "D20_68") (pintype "passive"))
    )
    (net (code "98") (name "/D21") (class "Default")
      (node (ref "IC1") (pin "152") (pinfunction "D21_152") (pintype "passive"))
      (node (ref "PL1") (pin "69") (pinfunction "D21_69") (pintype "passive"))
    )
    (net (code "99") (name "/D22") (class "Default")
      (node (ref "IC1") (pin "154") (pinfunction "D22_154") (pintype "passive"))
      (node (ref "PL1") (pin "70") (pinfunction "D22_70") (pintype "passive"))
    )
    (net (code "100") (name "/D23") (class "Default")
      (node (ref "IC1") (pin "155") (pinfunction "D23_155") (pintype "passive"))
      (node (ref "PL1") (pin "71") (pinfunction "D23_71") (pintype "passive"))
    )
    (net (code "101") (name "/D24") (class "Default")
      (node (ref "IC1") (pin "156") (pinfunction "D24_156") (pintype "passive"))
      (node (ref "PL1") (pin "72") (pinfunction "D24_72") (pintype "passive"))
    )
    (net (code "102") (name "/D25") (class "Default")
      (node (ref "IC1") (pin "157") (pinfunction "D25_157") (pintype "passive"))
      (node (ref "PL1") (pin "73") (pinfunction "D25_73") (pintype "passive"))
    )
    (net (code "103") (name "/D26") (class "Default")
      (node (ref "IC1") (pin "158") (pinfunction "D26_158") (pintype "passive"))
      (node (ref "PL1") (pin "74") (pinfunction "D26_74") (pintype "passive"))
    )
    (net (code "104") (name "/D27") (class "Default")
      (node (ref "IC1") (pin "1") (pinfunction "D27_1") (pintype "passive"))
      (node (ref "PL1") (pin "77") (pinfunction "D27_77") (pintype "passive"))
    )
    (net (code "105") (name "/D28") (class "Default")
      (node (ref "IC1") (pin "2") (pinfunction "D28_2") (pintype "passive"))
      (node (ref "PL1") (pin "78") (pinfunction "D28_78") (pintype "passive"))
    )
    (net (code "106") (name "/D29") (class "Default")
      (node (ref "IC1") (pin "3") (pinfunction "D29_3") (pintype "passive"))
      (node (ref "PL1") (pin "79") (pinfunction "D29_79") (pintype "passive"))
    )
    (net (code "107") (name "/D30") (class "Default")
      (node (ref "IC1") (pin "4") (pinfunction "D30_4") (pintype "passive"))
      (node (ref "PL1") (pin "80") (pinfunction "D30_80") (pintype "passive"))
    )
    (net (code "108") (name "/D31") (class "Default")
      (node (ref "IC1") (pin "5") (pinfunction "D31_5") (pintype "passive"))
      (node (ref "PL1") (pin "81") (pinfunction "D31_81") (pintype "passive"))
    )
    (net (code "109") (name "/DBE") (class "Default")
      (node (ref "IC1") (pin "30") (pinfunction "DBE_30") (pintype "passive"))
      (node (ref "PL1") (pin "83") (pinfunction "DBE_83") (pintype "passive"))
    )
    (net (code "111") (name "/HSCLK") (class "Default")
      (node (ref "IC2") (pin "3") (pinfunction "1CLK_3") (pintype "passive"))
      (node (ref "R6") (pin "1") (pinfunction "1_1") (pintype "passive"))
      (node (ref "X1") (pin "3") (pinfunction "3_3") (pintype "passive"))
      (node (ref "X2") (pin "3") (pinfunction "OUTPUT_3") (pintype "passive"))
    )
    (net (code "112") (name "/M0") (class "Default")
      (node (ref "IC1") (pin "12") (pinfunction "/M0_12") (pintype "passive"))
      (node (ref "PL1") (pin "14") (pinfunction "/M0_14") (pintype "passive"))
    )
    (net (code "113") (name "/M1") (class "Default")
      (node (ref "IC1") (pin "16") (pinfunction "/M1_16") (pintype "passive"))
      (node (ref "PL1") (pin "13") (pinfunction "/M1_13") (pintype "passive"))
    )
    (net (code "114") (name "/Opc") (class "Default")
      (node (ref "IC1") (pin "74") (pinfunction "/OPC_74") (pintype "passive"))
      (node (ref "SK1") (pin "43") (pinfunction "Opc_43") (pintype "passive"))
    )
    (net (code "115") (name "/PHI2") (class "Default")
      (node (ref "IC1") (pin "23") (pinfunction "MCLK_23") (pintype "passive"))
      (node (ref "PL1") (pin "1") (pinfunction "PHI2_1") (pintype "passive"))
    )
    (net (code "116") (name "/RST") (class "Default")
      (node (ref "IC2") (pin "13") (pinfunction "2~{CLR}_13") (pintype "passive"))
      (node (ref "PL1") (pin "9") (pinfunction "RES_9") (pintype "passive"))
    )
    (net (code "117") (name "/SEQ") (class "Default")
      (node (ref "IC1") (pin "20") (pinfunction "SEQ_20") (pintype "passive"))
      (node (ref "PL1") (pin "15") (pinfunction "SEQ_15") (pintype "passive"))
    )
    (net (code "118") (name "/TRANS") (class "Default")
      (node (ref "IC1") (pin "9") (pinfunction "/TRANS_9") (pintype "passive"))
      (node (ref "PL1") (pin "10") (pinfunction "/TRAN_10") (pintype "passive"))
    )
    (net (code "119") (name "/{slash}ARST") (class "Default")
      (node (ref "IC1") (pin "32") (pinfunction "/RESET_32") (pintype "passive"))
      (node (ref "IC2") (pin "8") (pinfunction "2~{Q}_8") (pintype "passive"))
      (node (ref "SK1") (pin "49") (pinfunction "Reset_49") (pintype "passive"))
    )
    (net (code "120") (name "/{slash}B{slash}W") (class "Default")
      (node (ref "IC1") (pin "6") (pinfunction "/B/W_6") (pintype "passive"))
      (node (ref "PL1") (pin "84") (pinfunction "/B/W_84") (pintype "passive"))
    )
    (net (code "121") (name "/{slash}FIQ") (class "Default")
      (node (ref "IC1") (pin "17") (pinfunction "/FIQ_17") (pintype "passive"))
      (node (ref "PL1") (pin "8") (pinfunction "/FIRQ_8") (pintype "passive"))
    )
    (net (code "122") (name "/{slash}IRQ") (class "Default")
      (node (ref "IC1") (pin "18") (pinfunction "/IRQ_18") (pintype "passive"))
      (node (ref "PL1") (pin "7") (pinfunction "/IRQ_7") (pintype "passive"))
    )
    (net (code "123") (name "/{slash}MEMRQ") (class "Default")
      (node (ref "IC1") (pin "21") (pinfunction "/MREQ_21") (pintype "passive"))
      (node (ref "PL1") (pin "5") (pinfunction "/MREQ_5") (pintype "passive"))
    )
    (net (code "124") (name "/{slash}R{slash}W") (class "Default")
      (node (ref "IC1") (pin "7") (pinfunction "/R/W_7") (pintype "passive"))
      (node (ref "PL1") (pin "3") (pinfunction "/R/W_3") (pintype "passive"))
    )
    (net (code "125") (name "GND") (class "Default")
      (node (ref "C1") (pin "2") (pinfunction "2_2") (pintype "passive"))
      (node (ref "C10") (pin "2") (pinfunction "2_2") (pintype "passive"))
      (node (ref "C11") (pin "2") (pinfunction "2_2") (pintype "passive"))
      (node (ref "C12") (pin "2") (pinfunction "2_2") (pintype "passive"))
      (node (ref "C13") (pin "2") (pinfunction "2_2") (pintype "passive"))
      (node (ref "C14") (pin "2") (pinfunction "2_2") (pintype "passive"))
      (node (ref "C15") (pin "2") (pinfunction "2_2") (pintype "passive"))
      (node (ref "C16") (pin "2") (pinfunction "2_2") (pintype "passive"))
      (node (ref "C17") (pin "2") (pinfunction "2_2") (pintype "passive"))
      (node (ref "C18") (pin "2") (pinfunction "2_2") (pintype "passive"))
      (node (ref "C19") (pin "2") (pinfunction "2_2") (pintype "passive"))
      (node (ref "C2") (pin "2") (pinfunction "2_2") (pintype "passive"))
      (node (ref "C20") (pin "2") (pinfunction "2_2") (pintype "passive"))
      (node (ref "C21") (pin "2") (pinfunction "2_2") (pintype "passive"))
      (node (ref "C22") (pin "2") (pinfunction "2_2") (pintype "passive"))
      (node (ref "C23") (pin "2") (pinfunction "2_2") (pintype "passive"))
      (node (ref "C3") (pin "2") (pinfunction "2_2") (pintype "passive"))
      (node (ref "C4") (pin "2") (pinfunction "2_2") (pintype "passive"))
      (node (ref "C5") (pin "2") (pinfunction "2_2") (pintype "passive"))
      (node (ref "C6") (pin "2") (pinfunction "2_2") (pintype "passive"))
      (node (ref "C7") (pin "2") (pinfunction "2_2") (pintype "passive"))
      (node (ref "C8") (pin "2") (pinfunction "2_2") (pintype "passive"))
      (node (ref "C9") (pin "2") (pinfunction "2_2") (pintype "passive"))
      (node (ref "IC1") (pin "103") (pinfunction "GND_103") (pintype "passive"))
      (node (ref "IC1") (pin "116") (pinfunction "GND_116") (pintype "passive"))
      (node (ref "IC1") (pin "129") (pinfunction "GND_129") (pintype "passive"))
      (node (ref "IC1") (pin "140") (pinfunction "GND_140") (pintype "passive"))
      (node (ref "IC1") (pin "149") (pinfunction "GND_149") (pintype "passive"))
      (node (ref "IC1") (pin "15") (pinfunction "GND_15") (pintype "passive"))
      (node (ref "IC1") (pin "160") (pinfunction "GND_160") (pintype "passive"))
      (node (ref "IC1") (pin "24") (pinfunction "GND_24") (pintype "passive"))
      (node (ref "IC1") (pin "39") (pinfunction "GND_39") (pintype "passive"))
      (node (ref "IC1") (pin "53") (pinfunction "GND_53") (pintype "passive"))
      (node (ref "IC1") (pin "69") (pinfunction "GBD_69") (pintype "passive"))
      (node (ref "IC1") (pin "80") (pinfunction "GND_80") (pintype "passive"))
      (node (ref "IC1") (pin "86") (pinfunction "GND_86") (pintype "passive"))
      (node (ref "IC1") (pin "90") (pinfunction "GND_90") (pintype "passive"))
      (node (ref "IC2") (pin "10") (pinfunction "2~{PRE}_10") (pintype "passive"))
      (node (ref "IC2") (pin "11") (pinfunction "2CLK_11") (pintype "passive"))
      (node (ref "IC2") (pin "12") (pinfunction "2D_12") (pintype "passive"))
      (node (ref "IC2") (pin "7") (pinfunction "GND_7") (pintype "passive"))
      (node (ref "IC3") (pin "3") (pinfunction "GND_3") (pintype "power_in"))
      (node (ref "PL1") (pin "33") (pinfunction "GND_33") (pintype "passive"))
      (node (ref "PL1") (pin "54") (pinfunction "GND_54") (pintype "passive"))
      (node (ref "PL1") (pin "75") (pinfunction "GND_75") (pintype "passive"))
      (node (ref "RN2") (pin "8") (pinfunction "8_8") (pintype "passive"))
      (node (ref "SK1") (pin "11") (pintype "passive"))
      (node (ref "SK1") (pin "15") (pintype "passive"))
      (node (ref "SK1") (pin "19") (pintype "passive"))
      (node (ref "SK1") (pin "23") (pintype "passive"))
      (node (ref "SK1") (pin "26") (pintype "passive"))
      (node (ref "SK1") (pin "32") (pintype "passive"))
      (node (ref "SK1") (pin "39") (pintype "passive"))
      (node (ref "SK1") (pin "4") (pintype "passive"))
      (node (ref "SK1") (pin "47") (pintype "passive"))
      (node (ref "SK1") (pin "55") (pintype "passive"))
      (node (ref "SK1") (pin "65") (pintype "passive"))
      (node (ref "X1") (pin "2") (pinfunction "2_2") (pintype "passive"))
      (node (ref "X2") (pin "2") (pinfunction "GND_2") (pintype "passive"))
    )
    (net (code "126") (name "Net-(IC2-1D)") (class "Default")
      (node (ref "IC2") (pin "2") (pinfunction "1D_2") (pintype "passive"))
      (node (ref "IC2") (pin "6") (pinfunction "1~{Q}_6") (pintype "passive"))
    )
    (net (code "127") (name "Net-(IC2-1Q)") (class "Default")
      (node (ref "IC2") (pin "5") (pinfunction "1Q_5") (pintype "passive"))
      (node (ref "R1") (pin "1") (pinfunction "1_1") (pintype "passive"))
    )
    (net (code "128") (name "Net-(IC3-XTALIN)") (class "Default")
      (node (ref "IC3") (pin "8") (pinfunction "XTALIN_8") (pintype "input"))
      (node (ref "Y1") (pin "2") (pinfunction "2_2") (pintype "passive"))
    )
    (net (code "129") (name "Net-(IC3-XTALOUT)") (class "Default")
      (node (ref "IC3") (pin "1") (pinfunction "XTALOUT_1") (pintype "output"))
      (node (ref "Y1") (pin "1") (pinfunction "1_1") (pintype "passive"))
    )
    (net (code "130") (name "Net-(SK1-Tck)") (class "Default")
      (node (ref "RN2") (pin "4") (pinfunction "4_4") (pintype "passive"))
      (node (ref "SK1") (pin "54") (pinfunction "Tck_54") (pintype "passive"))
    )
    (net (code "131") (name "Net-(SK1-Tdi)") (class "Default")
      (node (ref "RN2") (pin "2") (pinfunction "2_2") (pintype "passive"))
      (node (ref "SK1") (pin "58") (pinfunction "Tdi_58") (pintype "passive"))
    )
    (net (code "132") (name "Net-(SK1-Tms)") (class "Default")
      (node (ref "RN2") (pin "3") (pinfunction "3_3") (pintype "passive"))
      (node (ref "SK1") (pin "57") (pinfunction "Tms_57") (pintype "passive"))
    )
    (net (code "133") (name "Net-(SK1-Trst)") (class "Default")
      (node (ref "RN2") (pin "1") (pinfunction "1_1") (pintype "passive"))
      (node (ref "SK1") (pin "59") (pinfunction "Trst_59") (pintype "passive"))
    )
    (net (code "134") (name "VCC") (class "Default")
      (node (ref "C1") (pin "1") (pinfunction "1_1") (pintype "passive"))
      (node (ref "C10") (pin "1") (pinfunction "1_1") (pintype "passive"))
      (node (ref "C11") (pin "1") (pinfunction "1_1") (pintype "passive"))
      (node (ref "C12") (pin "1") (pinfunction "1_1") (pintype "passive"))
      (node (ref "C13") (pin "1") (pinfunction "1_1") (pintype "passive"))
      (node (ref "C14") (pin "1") (pinfunction "1_1") (pintype "passive"))
      (node (ref "C15") (pin "1") (pinfunction "1_1") (pintype "passive"))
      (node (ref "C16") (pin "1") (pinfunction "1_1") (pintype "passive"))
      (node (ref "C17") (pin "1") (pinfunction "1_1") (pintype "passive"))
      (node (ref "C18") (pin "1") (pinfunction "1_1") (pintype "passive"))
      (node (ref "C19") (pin "1") (pinfunction "1_1") (pintype "passive"))
      (node (ref "C2") (pin "1") (pinfunction "1_1") (pintype "passive"))
      (node (ref "C20") (pin "1") (pinfunction "1_1") (pintype "passive"))
      (node (ref "C21") (pin "1") (pinfunction "1_1") (pintype "passive"))
      (node (ref "C22") (pin "1") (pinfunction "1_1") (pintype "passive"))
      (node (ref "C23") (pin "1") (pinfunction "1_1") (pintype "passive"))
      (node (ref "C3") (pin "1") (pinfunction "1_1") (pintype "passive"))
      (node (ref "C4") (pin "1") (pinfunction "1_1") (pintype "passive"))
      (node (ref "C5") (pin "1") (pinfunction "1_1") (pintype "passive"))
      (node (ref "C6") (pin "1") (pinfunction "1_1") (pintype "passive"))
      (node (ref "C7") (pin "1") (pinfunction "1_1") (pintype "passive"))
      (node (ref "C8") (pin "1") (pinfunction "1_1") (pintype "passive"))
      (node (ref "C9") (pin "1") (pinfunction "1_1") (pintype "passive"))
      (node (ref "IC1") (pin "102") (pinfunction "VDD_102") (pintype "passive"))
      (node (ref "IC1") (pin "122") (pinfunction "VDD_122") (pintype "passive"))
      (node (ref "IC1") (pin "13") (pinfunction "VDD_13") (pintype "passive"))
      (node (ref "IC1") (pin "139") (pinfunction "VDD_139") (pintype "passive"))
      (node (ref "IC1") (pin "141") (pinfunction "VDD_141") (pintype "passive"))
      (node (ref "IC1") (pin "159") (pinfunction "VDD_159") (pintype "passive"))
      (node (ref "IC1") (pin "25") (pinfunction "VDD_25") (pintype "passive"))
      (node (ref "IC1") (pin "41") (pinfunction "VDD_41") (pintype "passive"))
      (node (ref "IC1") (pin "55") (pinfunction "VDD_55") (pintype "passive"))
      (node (ref "IC1") (pin "78") (pinfunction "VDD_78") (pintype "passive"))
      (node (ref "IC1") (pin "87") (pinfunction "VDD_87") (pintype "passive"))
      (node (ref "IC2") (pin "1") (pinfunction "1~{CLR}_1") (pintype "passive"))
      (node (ref "IC2") (pin "14") (pinfunction "VCC_14") (pintype "passive"))
      (node (ref "IC2") (pin "4") (pinfunction "1~{PRE}_4") (pintype "passive"))
      (node (ref "IC3") (pin "6") (pinfunction "VDD_6") (pintype "power_in"))
      (node (ref "IC3") (pin "7") (pinfunction "MUXREF/OE_7") (pintype "input"))
      (node (ref "PL1") (pin "11") (pinfunction "VCC_11") (pintype "passive"))
      (node (ref "PL1") (pin "32") (pinfunction "VCC_32") (pintype "passive"))
      (node (ref "PL1") (pin "55") (pinfunction "VCC_55") (pintype "passive"))
      (node (ref "PL1") (pin "82") (pinfunction "/CPI_82") (pintype "passive"))
      (node (ref "R2") (pin "1") (pinfunction "1_1") (pintype "passive"))
      (node (ref "R3") (pin "2") (pinfunction "2_2") (pintype "passive"))
      (node (ref "R4") (pin "2") (pinfunction "2_2") (pintype "passive"))
      (node (ref "RN1") (pin "5") (pinfunction "5_5") (pintype "passive"))
      (node (ref "RN1") (pin "6") (pinfunction "6_6") (pintype "passive"))
      (node (ref "RN1") (pin "7") (pinfunction "7_7") (pintype "passive"))
      (node (ref "RN1") (pin "8") (pinfunction "8_8") (pintype "passive"))
      (node (ref "RN2") (pin "5") (pinfunction "5_5") (pintype "passive"))
      (node (ref "RN2") (pin "6") (pinfunction "6_6") (pintype "passive"))
      (node (ref "RN2") (pin "7") (pinfunction "7_7") (pintype "passive"))
      (node (ref "SK1") (pin "14") (pintype "passive"))
      (node (ref "SK1") (pin "18") (pintype "passive"))
      (node (ref "SK1") (pin "22") (pintype "passive"))
      (node (ref "SK1") (pin "31") (pintype "passive"))
      (node (ref "SK1") (pin "38") (pintype "passive"))
      (node (ref "SK1") (pin "5") (pintype "passive"))
      (node (ref "SK1") (pin "56") (pintype "passive"))
      (node (ref "SK1") (pin "66") (pintype "passive"))
      (node (ref "X1") (pin "4") (pinfunction "4_4") (pintype "passive"))
      (node (ref "X2") (pin "4") (pinfunction "+VS_4") (pintype "passive"))
    )
    (net (code "135") (name "unconnected-(IC1-LINE-Pad10)") (class "Default")
      (node (ref "IC1") (pin "10") (pinfunction "LINE_10") (pintype "passive+no_connect"))
    )
    (net (code "136") (name "unconnected-(IC1-LOCK-Pad11)") (class "Default")
      (node (ref "IC1") (pin "11") (pinfunction "LOCK_11") (pintype "passive+no_connect"))
    )
    (net (code "137") (name "unconnected-(IC1-MSE-Pad19)") (class "Default")
      (node (ref "IC1") (pin "19") (pinfunction "MSE_19") (pintype "passive+no_connect"))
    )
    (net (code "138") (name "unconnected-(IC1-NC-Pad8)") (class "Default")
      (node (ref "IC1") (pin "8") (pinfunction "NC_8") (pintype "passive+no_connect"))
    )
    (net (code "139") (name "unconnected-(IC1-NC-Pad14)") (class "Default")
      (node (ref "IC1") (pin "14") (pinfunction "NC_14") (pintype "passive+no_connect"))
    )
    (net (code "140") (name "unconnected-(IC1-NC-Pad27)") (class "Default")
      (node (ref "IC1") (pin "27") (pinfunction "NC_27") (pintype "passive+no_connect"))
    )
    (net (code "141") (name "unconnected-(IC1-NC-Pad33)") (class "Default")
      (node (ref "IC1") (pin "33") (pinfunction "NC_33") (pintype "passive+no_connect"))
    )
    (net (code "142") (name "unconnected-(IC1-NC-Pad48)") (class "Default")
      (node (ref "IC1") (pin "48") (pinfunction "NC_48") (pintype "passive+no_connect"))
    )
    (net (code "143") (name "unconnected-(IC1-NC-Pad54)") (class "Default")
      (node (ref "IC1") (pin "54") (pinfunction "NC_54") (pintype "passive+no_connect"))
    )
    (net (code "144") (name "unconnected-(IC1-NC-Pad67)") (class "Default")
      (node (ref "IC1") (pin "67") (pinfunction "NC_67") (pintype "passive+no_connect"))
    )
    (net (code "145") (name "unconnected-(IC1-NC-Pad73)") (class "Default")
      (node (ref "IC1") (pin "73") (pinfunction "NC_73") (pintype "passive+no_connect"))
    )
    (net (code "146") (name "unconnected-(IC1-NC-Pad88)") (class "Default")
      (node (ref "IC1") (pin "88") (pinfunction "NC_88") (pintype "passive+no_connect"))
    )
    (net (code "147") (name "unconnected-(IC1-NC-Pad94)") (class "Default")
      (node (ref "IC1") (pin "94") (pinfunction "NC_94") (pintype "passive+no_connect"))
    )
    (net (code "148") (name "unconnected-(IC1-NC-Pad107)") (class "Default")
      (node (ref "IC1") (pin "107") (pinfunction "NC_107") (pintype "passive+no_connect"))
    )
    (net (code "149") (name "unconnected-(IC1-NC-Pad113)") (class "Default")
      (node (ref "IC1") (pin "113") (pinfunction "NC_113") (pintype "passive+no_connect"))
    )
    (net (code "150") (name "unconnected-(IC1-NC-Pad128)") (class "Default")
      (node (ref "IC1") (pin "128") (pinfunction "NC_128") (pintype "passive+no_connect"))
    )
    (net (code "151") (name "unconnected-(IC1-NC-Pad134)") (class "Default")
      (node (ref "IC1") (pin "134") (pinfunction "NC_134") (pintype "passive+no_connect"))
    )
    (net (code "152") (name "unconnected-(IC1-NC-Pad147)") (class "Default")
      (node (ref "IC1") (pin "147") (pinfunction "NC_147") (pintype "passive+no_connect"))
    )
    (net (code "153") (name "unconnected-(IC1-NC-Pad153)") (class "Default")
      (node (ref "IC1") (pin "153") (pinfunction "NC_153") (pintype "passive+no_connect"))
    )
    (net (code "154") (name "unconnected-(IC1-{slash}TEST-Pad35)") (class "Default")
      (node (ref "IC1") (pin "35") (pinfunction "/TEST_35") (pintype "passive+no_connect"))
    )
    (net (code "155") (name "unconnected-(IC1-{slash}WAIT-Pad34)") (class "Default")
      (node (ref "IC1") (pin "34") (pinfunction "/WAIT_34") (pintype "passive+no_connect"))
    )
    (net (code "156") (name "unconnected-(IC2-2Q-Pad9)") (class "Default")
      (node (ref "IC2") (pin "9") (pinfunction "2Q_9") (pintype "passive+no_connect"))
    )
    (net (code "157") (name "unconnected-(PL1-CPA-Pad76)") (class "Default")
      (node (ref "PL1") (pin "76") (pinfunction "CPA_76") (pintype "passive+no_connect"))
    )
    (net (code "158") (name "unconnected-(PL1-CPB-Pad12)") (class "Default")
      (node (ref "PL1") (pin "12") (pinfunction "CPB_12") (pintype "passive+no_connect"))
    )
    (net (code "159") (name "unconnected-(PL1-PHI1-Pad2)") (class "Default")
      (node (ref "PL1") (pin "2") (pinfunction "PHI1_2") (pintype "passive+no_connect"))
    )
    (net (code "160") (name "unconnected-(PL1-{slash}OPC-Pad4)") (class "Default")
      (node (ref "PL1") (pin "4") (pinfunction "/OPC_4") (pintype "passive+no_connect"))
    )
    (net (code "161") (name "unconnected-(SK1-NC-Pad60)") (class "Default")
      (node (ref "SK1") (pin "60") (pinfunction "NC_60") (pintype "passive+no_connect"))
    )
    (net (code "162") (name "unconnected-(SK1-Tdo-Pad53)") (class "Default")
      (node (ref "SK1") (pin "53") (pinfunction "Tdo_53") (pintype "passive+no_connect"))
    )
    (net (code "163") (name "unconnected-(X1-Pad1)") (class "Default")
      (node (ref "X1") (pin "1") (pinfunction "1_1") (pintype "passive+no_connect"))
    )
    (net (code "164") (name "unconnected-(X2-STANDBY_OPERATION-Pad1)") (class "Default")
      (node (ref "X2") (pin "1") (pinfunction "STANDBY_OPERATION_1") (pintype "passive+no_connect"))
    )
  )
)
